# Sheet_rectifier_updated.net
KiCad netlist of a schematic drawn in Altium Designer
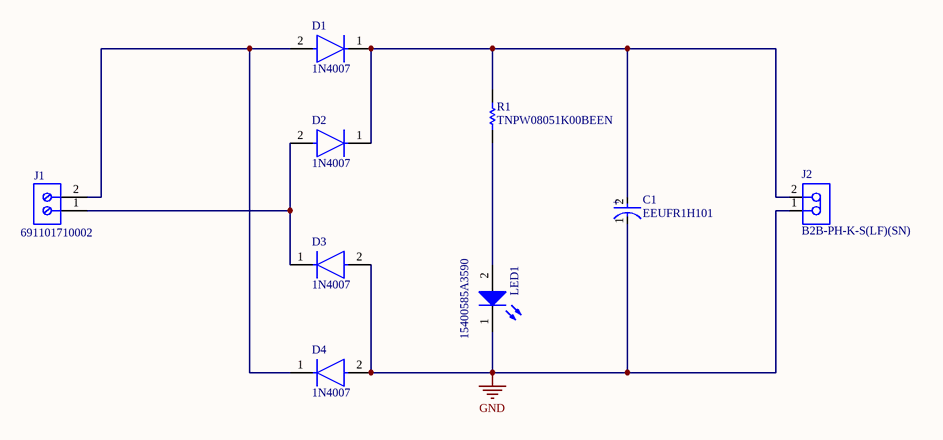
[diagram p0: Sheet_rectifier_updated.SchDoc]

(export (version "E")
  (design (tool "Eeschema 10.0.6"))
  (components
    (comp (ref "C1")
      (value "EEUFR1H101")
      (footprint "FP-RAD-TH-D_8_0_5-L_11_5-MFG")
      (description "Aluminum Electrolytic Capacitors (Radial Lead Type) 100uF ±20% 50V")
      (fields (field (name "VOLTAGE") "50V") (field (name "TOLERANCE") "20%"))
      (libsource (lib "Altium Content Vault") (part "a00bbbee19879c290e62620ae7e47b1"))
    )
    (comp (ref "D1")
      (value "1N4007")
      (footprint "FP-1N4007-MFG")
      (description "Rectifier diode 1000 V 1 A DO-41, ,")
      (fields
        (field (name "MANUFACTURER") "Diotec")
        (field (name "OCTOPART") "https://octopart.com/1n4007-diotec-4040411")
      )
      (libsource (lib "Altium Content Vault") (part "d7152d700b627762746794eb795d46e"))
    )
    (comp (ref "D2")
      (value "1N4007")
      (footprint "FP-1N4007-MFG")
      (description "Rectifier diode 1000 V 1 A DO-41, ,")
      (fields
        (field (name "MANUFACTURER") "Diotec")
        (field (name "OCTOPART") "https://octopart.com/1n4007-diotec-4040411")
      )
      (libsource (lib "Altium Content Vault") (part "d7152d700b627762746794eb795d46e"))
    )
    (comp (ref "D3")
      (value "1N4007")
      (footprint "FP-1N4007-MFG")
      (description "Rectifier diode 1000 V 1 A DO-41, ,")
      (fields
        (field (name "MANUFACTURER") "Diotec")
        (field (name "OCTOPART") "https://octopart.com/1n4007-diotec-4040411")
      )
      (libsource (lib "Altium Content Vault") (part "d7152d700b627762746794eb795d46e"))
    )
    (comp (ref "D4")
      (value "1N4007")
      (footprint "FP-1N4007-MFG")
      (description "Rectifier diode 1000 V 1 A DO-41, ,")
      (fields
        (field (name "MANUFACTURER") "Diotec")
        (field (name "OCTOPART") "https://octopart.com/1n4007-diotec-4040411")
      )
      (libsource (lib "Altium Content Vault") (part "d7152d700b627762746794eb795d46e"))
    )
    (comp (ref "J1")
      (value "691101710002")
      (footprint "691101710002")
      (description "Conn Terminal Block 2 POS 5mm Solder ST Thru-Hole 16A Box")
      (fields (field (name "VOLTAGE") "250V"))
      (libsource (lib "Altium Content Vault") (part "TBL - 1R - 02P - Screw"))
    )
    (comp (ref "J2")
      (value "B2B-PH-K-S(LF)(SN)")
      (footprint "JST-B2B-PH-K-S_V")
      (fields (field (name "MANUFACTURER") "JST"))
      (libsource (lib "Altium Content Vault") (part "CN-2P-F-QF2"))
    )
    (comp (ref "LED1")
      (value "15400585A3590")
      (footprint "WL-TIRW_D5.8H8.6")
      (description "WL-TIRW THT Infrared Round Waterclear")
      (libsource (lib "Altium Content Vault") (part "LED_Infrared_2A-1K"))
    )
    (comp (ref "R1")
      (value "TNPW08051K00BEEN")
      (footprint "RESC2013X55X40LL15T20")
      (fields (field (name "MANUFACTURER") "Vishay Dale"))
      (libsource (lib "Altium Content Vault") (part "RES"))
    )
  )
  (nets
    (net (code "1") (name "GND") (class "Default")
      (node (ref "C1") (pin "1") (pinfunction "C_1") (pintype "passive"))
      (node (ref "D3") (pin "2") (pinfunction "A_2") (pintype "passive"))
      (node (ref "D4") (pin "2") (pinfunction "A_2") (pintype "passive"))
      (node (ref "J2") (pin "1") (pinfunction "1_1") (pintype "passive"))
      (node (ref "LED1") (pin "1") (pinfunction "K_1") (pintype "passive"))
    )
    (net (code "2") (name "Net-(C1-A)") (class "Default")
      (node (ref "C1") (pin "2") (pinfunction "A_2") (pintype "passive"))
      (node (ref "D1") (pin "1") (pinfunction "C_1") (pintype "passive"))
      (node (ref "D2") (pin "1") (pinfunction "C_1") (pintype "passive"))
      (node (ref "J2") (pin "2") (pinfunction "2_2") (pintype "passive"))
      (node (ref "R1") (pin "2") (pinfunction "2_2") (pintype "passive"))
    )
    (net (code "3") (name "Net-(D1-A)") (class "Default")
      (node (ref "D1") (pin "2") (pinfunction "A_2") (pintype "passive"))
      (node (ref "D4") (pin "1") (pinfunction "C_1") (pintype "passive"))
      (node (ref "J1") (pin "2") (pinfunction "2_2") (pintype "passive"))
    )
    (net (code "4") (name "Net-(D2-A)") (class "Default")
      (node (ref "D2") (pin "2") (pinfunction "A_2") (pintype "passive"))
      (node (ref "D3") (pin "1") (pinfunction "C_1") (pintype "passive"))
      (node (ref "J1") (pin "1") (pinfunction "1_1") (pintype "passive"))
    )
    (net (code "5") (name "Net-(LED1-A)") (class "Default")
      (node (ref "LED1") (pin "2") (pinfunction "A_2") (pintype "passive"))
      (node (ref "R1") (pin "1") (pinfunction "1_1") (pintype "passive"))
    )
  )
)
